# Power_Supply.net
KiCad netlist of a schematic drawn in Altium Designer
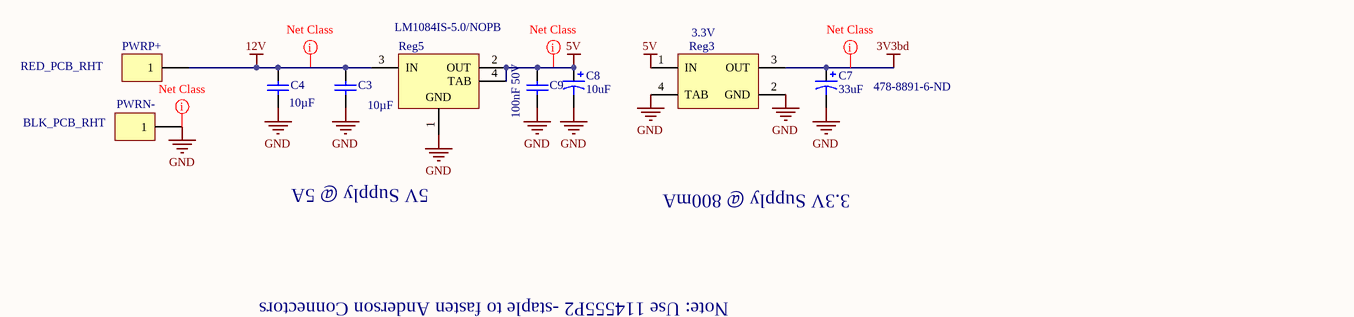
[diagram p0: Power Supply.SchDoc]

(export (version "E")
  (design (tool "Eeschema 10.0.6"))
  (components
    (comp (ref "C3")
      (value "10µF")
      (footprint "CAPC2013X135X45ML10T25")
      (fields
        (field (name "PART NUMBER") "GRM21BR61E106KA73L")
        (field (name "MANUFACTURER") "Murata")
        (field (name "TOLERANCE") "±10%")
      )
      (libsource (lib "Altium Content Vault") (part "CMP-2007-03541-1"))
    )
    (comp (ref "C4")
      (value "10µF")
      (footprint "CAPC2013X135X45ML10T25")
      (fields
        (field (name "PART NUMBER") "GRM21BR61E106KA73L")
        (field (name "MANUFACTURER") "Murata")
        (field (name "TOLERANCE") "±10%")
      )
      (libsource (lib "Altium Content Vault") (part "CMP-2007-03541-1"))
    )
    (comp (ref "C7")
      (value "33uF")
      (footprint "AVX-CAPC3528_V")
      (description "Capacitor, Tantalum, 10uF 10% 20V MCCT-B (3528)")
      (fields
        (field (name "SUPPLIER PART NUMBER 1") "478-8891-6-ND")
        (field (name "MANUFACTURER") "Kyocera / AVX")
        (field (name "MANUFACTURER PART NUMBER") "TAJB336K006RNJ")
      )
      (libsource (lib "Altium Content Vault") (part "CMP-0279-00001-1"))
    )
    (comp (ref "C8")
      (value "10uF")
      (footprint "AVX-CAPC3528_V")
      (description "Capacitor, Tantalum, 10uF 10% 20V MCCT-B (3528)")
      (fields (field (name "PARTNUMBER") "TAJB106K020R") (field (name "MANUFACTURER") "AVX"))
      (libsource (lib "Altium Content Vault") (part "CMP-0279-00001-1"))
    )
    (comp (ref "C9")
      (value "100nF 50V")
      (footprint "0603C_L")
      (fields
        (field (name "MANUFACTURER") "Yageo")
        (field (name "MANUFACTURER PART NUMBER") "CC0603ZRY5V9BB104")
        (field (name "TOLERANCE") "-20%, +80%")
      )
      (libsource (lib "PoleV2PaintV5") (part "Cap100nF_50V_0603"))
    )
    (comp (ref "PWRN-")
      (value "BLK_PCB_RHT")
      (footprint "Anderson_BLK_RHT_BOT")
      (description "1 pin Anderson")
      (fields
        (field (name "MANUFACTURER") "Anderson Power Products (APP)")
        (field (name "MANUFACTURER PART NUMBER") "1377G1, 1377G2, 1327-BK,137G6-BK")
      )
      (libsource (lib "WCT") (part "Anderson-1Pin BLK_PCB_RHT"))
    )
    (comp (ref "PWRP+")
      (value "RED_PCB_RHT")
      (footprint "Anderson_Red_RHT_BOT")
      (description "1 pin Anderson")
      (fields
        (field (name "MANUFACTURER") "Anderson Power Products (APP)")
        (field (name "MANUFACTURER PART NUMBER") "1377G1, 1377G2, 1327-BK,137G6-BK")
      )
      (libsource (lib "WCT") (part "Anderson-1Pin RED_PCB_RHT"))
    )
    (comp (ref "Reg3")
      (value "3.3V")
      (footprint "DCY0004A_M")
      (description "1A Low Dropout Regulator for 5V to 3.3V Conversion, 4-pin SOT-223, Pb-Free")
      (fields
        (field (name "MANUFACTURER") "Texas Instruments")
        (field (name "MANUFACTURER PART NUMBER") "LM3940IMP-3.3/NOPB")
      )
      (libsource (lib "Altium Content Vault") (part "CMP-0062-01788-3"))
    )
    (comp (ref "Reg5")
      (value "LM1084IS-5.0/NOPB")
      (footprint "KTT0003B_L")
      (description "5A Low Dropout Positive Regulators, 3-pin TO-263, Pb-Free")
      (fields (field (name "MANUFACTURER") "Texas Instruments"))
      (libsource (lib "Altium Content Vault") (part "CMP-0062-00575-4"))
    )
  )
  (nets
    (net (code "1") (name "3V3bd") (class "Default")
      (node (ref "C7") (pin "1") (pinfunction "1_1") (pintype "passive"))
      (node (ref "Reg3") (pin "3") (pinfunction "OUT_3") (pintype "power_in"))
    )
    (net (code "2") (name "5V") (class "Default")
      (node (ref "C8") (pin "1") (pinfunction "1_1") (pintype "passive"))
      (node (ref "C9") (pin "2") (pinfunction "2_2") (pintype "passive"))
      (node (ref "Reg3") (pin "1") (pinfunction "IN_1") (pintype "power_in"))
      (node (ref "Reg5") (pin "2") (pinfunction "OUT_2") (pintype "power_in"))
      (node (ref "Reg5") (pin "4") (pinfunction "TAB_4") (pintype "power_in"))
    )
    (net (code "3") (name "12V") (class "Default")
      (node (ref "C3") (pin "2") (pinfunction "2_2") (pintype "passive"))
      (node (ref "C4") (pin "2") (pinfunction "2_2") (pintype "passive"))
      (node (ref "PWRP+") (pin "1") (pinfunction "1_1") (pintype "passive"))
      (node (ref "Reg5") (pin "3") (pinfunction "IN_3") (pintype "power_in"))
    )
    (net (code "4") (name "GND") (class "Default")
      (node (ref "C3") (pin "1") (pinfunction "1_1") (pintype "passive"))
      (node (ref "C4") (pin "1") (pinfunction "1_1") (pintype "passive"))
      (node (ref "C7") (pin "2") (pinfunction "2_2") (pintype "passive"))
      (node (ref "C8") (pin "2") (pinfunction "2_2") (pintype "passive"))
      (node (ref "C9") (pin "1") (pinfunction "1_1") (pintype "passive"))
      (node (ref "PWRN-") (pin "1") (pinfunction "1_1") (pintype "passive"))
      (node (ref "Reg3") (pin "2") (pinfunction "GND_2") (pintype "power_in"))
      (node (ref "Reg3") (pin "4") (pinfunction "TAB_4") (pintype "power_in"))
      (node (ref "Reg5") (pin "1") (pinfunction "GND_1") (pintype "power_in"))
    )
  )
)
